# PROC054D_AWR_2_AWR_3_LP87524P.net
KiCad netlist of a schematic drawn in Altium Designer
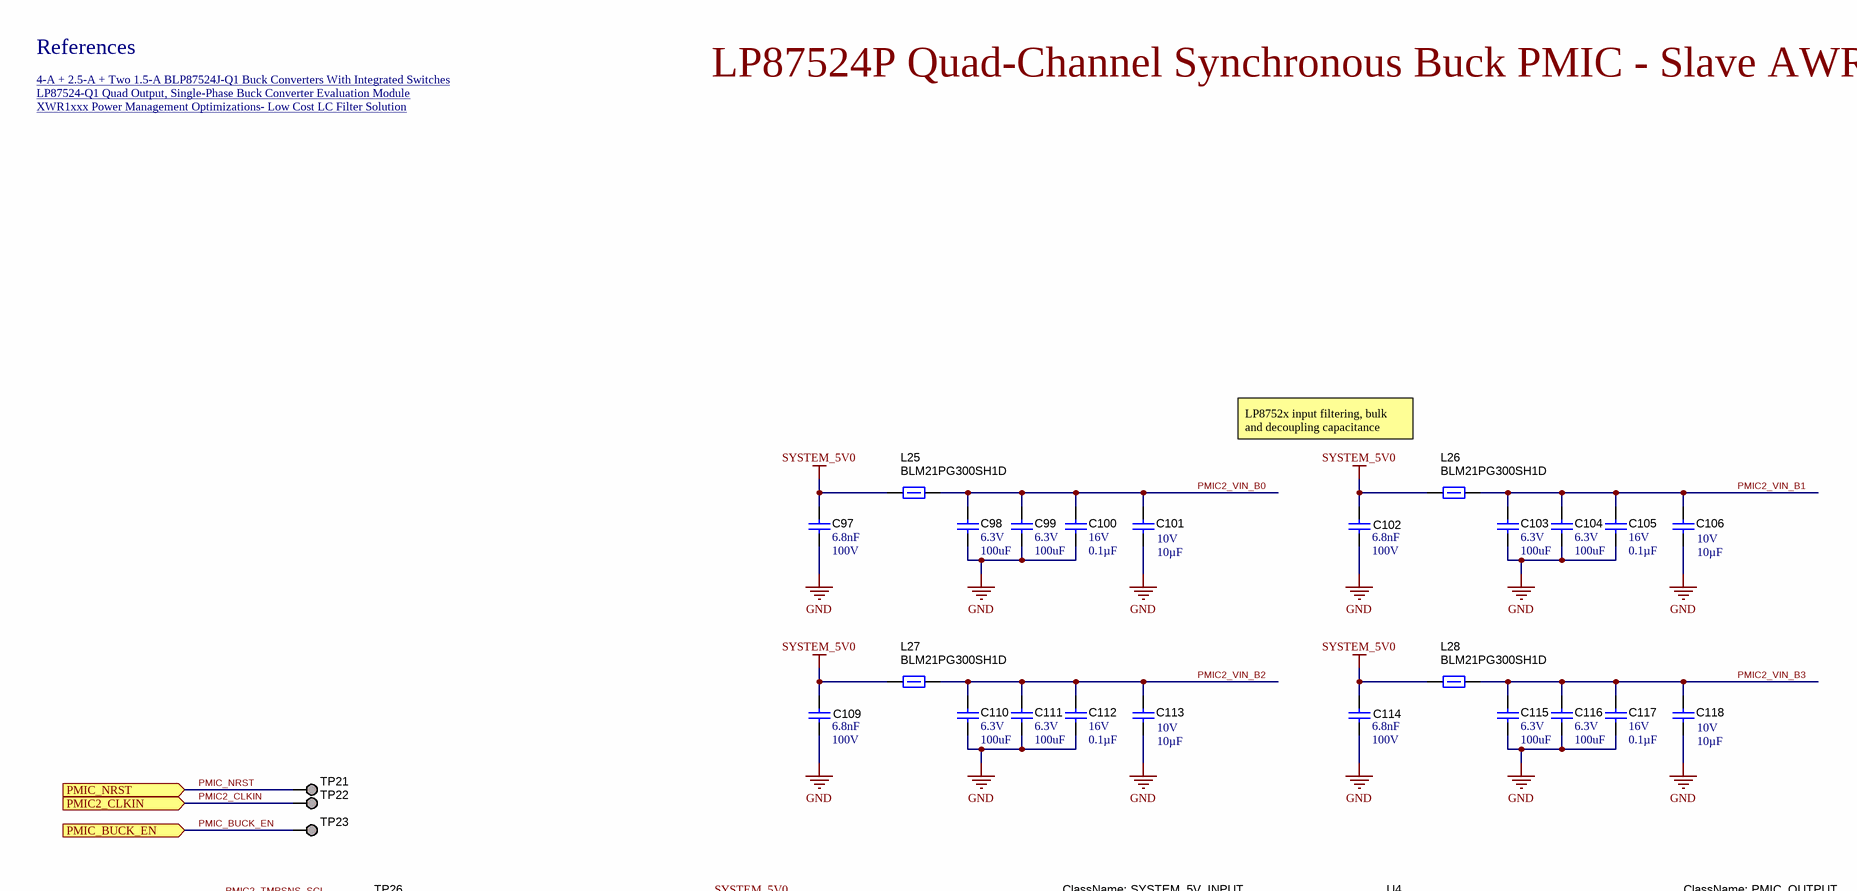
[diagram p0: PROC054D_AWR_2_AWR_3_LP87524P.SchDoc, top left]
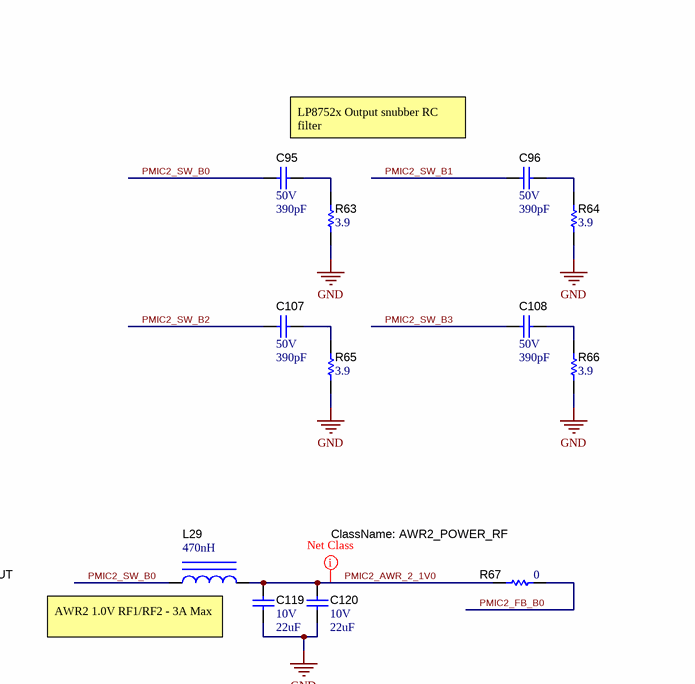
[diagram p1: PROC054D_AWR_2_AWR_3_LP87524P.SchDoc, top right]
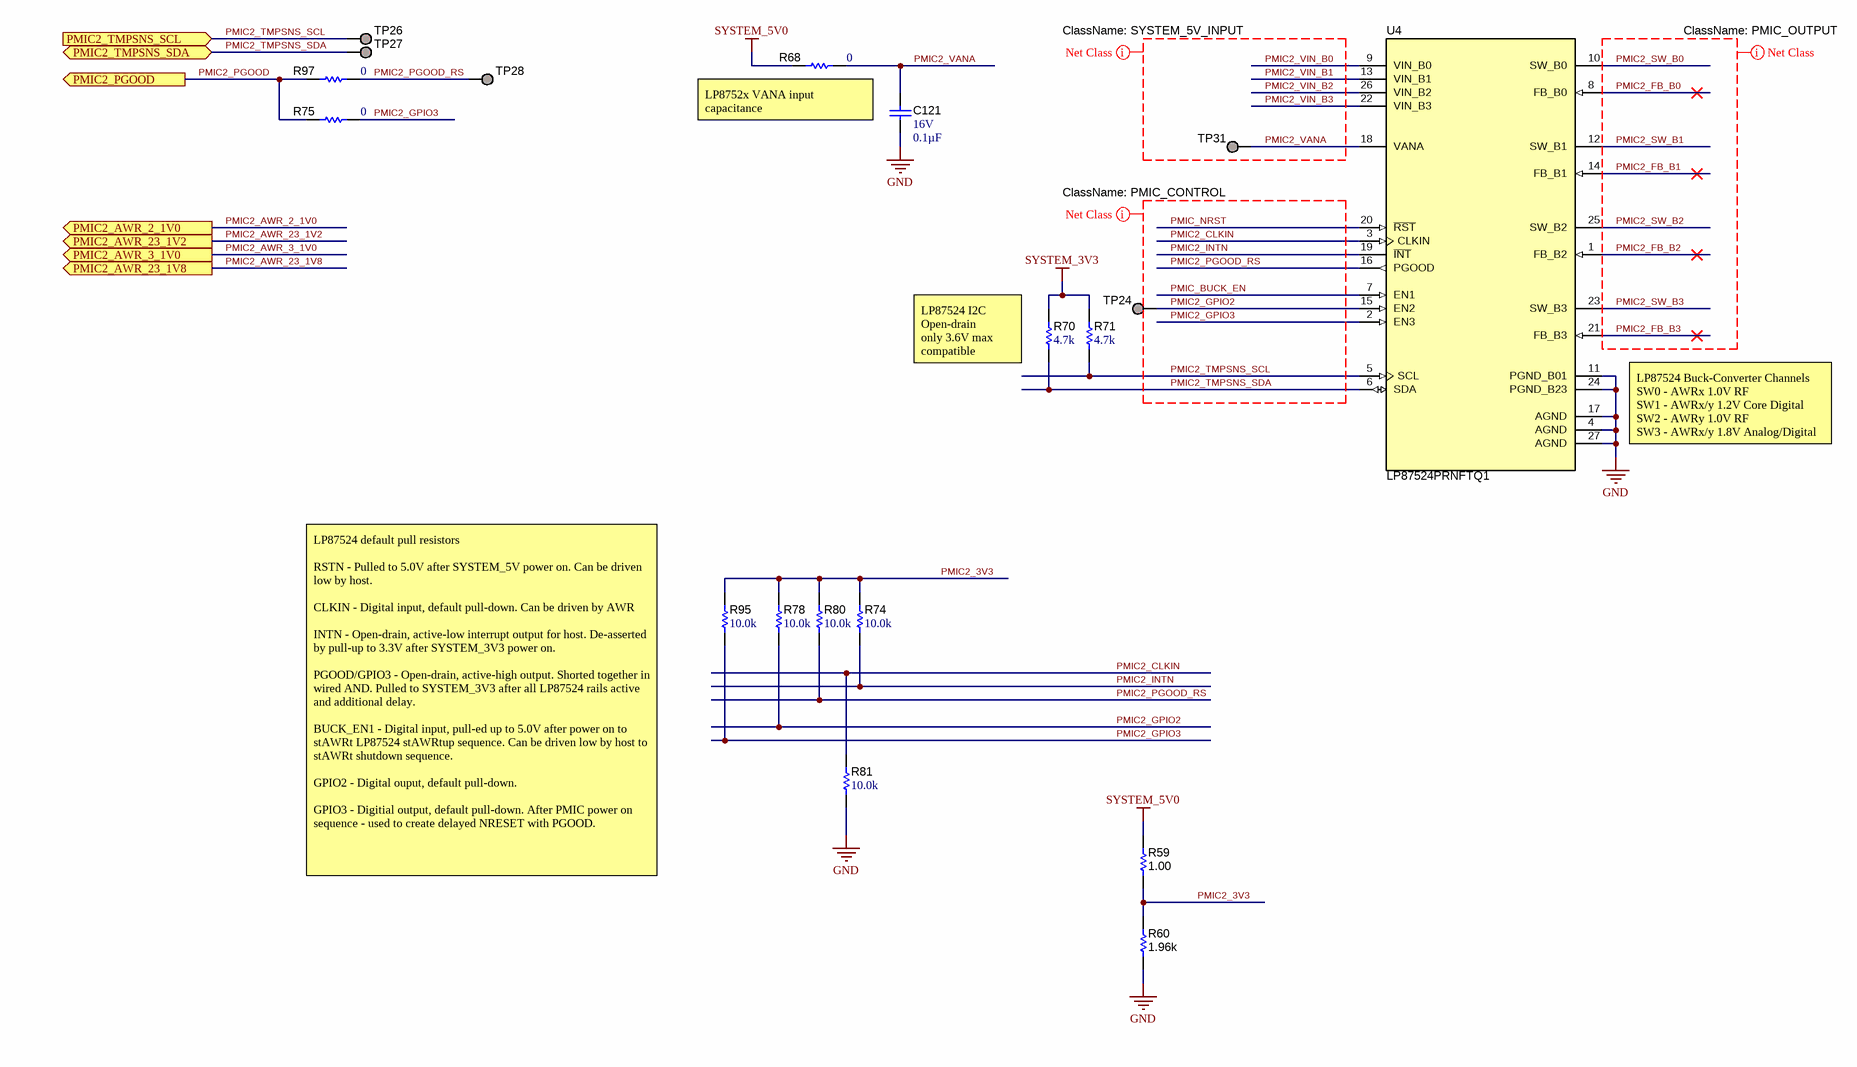
[diagram p2: PROC054D_AWR_2_AWR_3_LP87524P.SchDoc, bottom left]
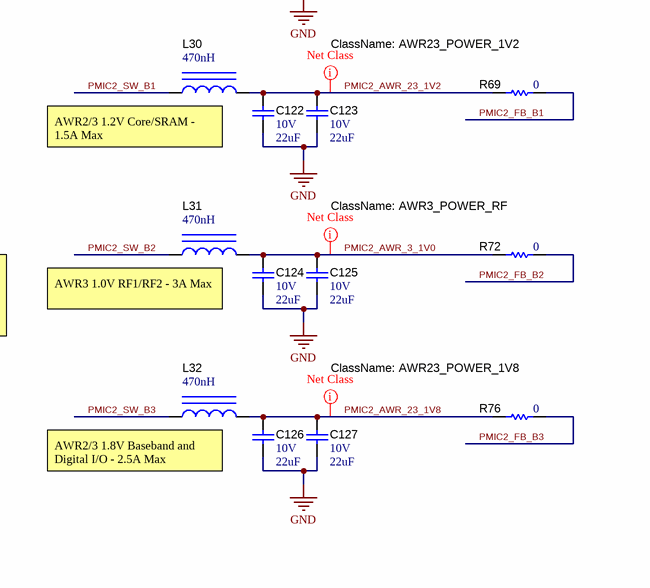
[diagram p3: PROC054D_AWR_2_AWR_3_LP87524P.SchDoc, bottom right]

(export (version "E")
  (design (tool "Eeschema 10.0.6"))
  (components
    (comp (ref "C95")
      (value "GCM155R71H391KA37D")
      (footprint "0402S")
      (description "CAP, CERM, 390 pF, 50 V,+/- 10%, X7R, AEC-Q200 Grade 1, 0402")
      (fields
        (field (name "MANUFACTURER") "MuRata")
        (field (name "VDC_V") "50V")
        (field (name "VALUEDISPLAYED") "390pF")
      )
      (libsource (lib "Altium Vault - TI") (part "Capacitor"))
    )
    (comp (ref "C96")
      (value "GCM155R71H391KA37D")
      (footprint "0402S")
      (description "CAP, CERM, 390 pF, 50 V,+/- 10%, X7R, AEC-Q200 Grade 1, 0402")
      (fields
        (field (name "MANUFACTURER") "MuRata")
        (field (name "VDC_V") "50V")
        (field (name "VALUEDISPLAYED") "390pF")
      )
      (libsource (lib "Altium Vault - TI") (part "Capacitor"))
    )
    (comp (ref "C97")
      (value "GCM188R72A682KA37D")
      (footprint "0603S")
      (description "CAP, CERM, 6800 pF, 100 V,+/- 10%, X7R, AEC-Q200 Grade 1, 0603")
      (fields
        (field (name "CAP_F") "6.8nF")
        (field (name "VDC_V") "100V")
        (field (name "MANUFACTURER") "MuRata")
      )
      (libsource (lib "Altium Vault - TI") (part "Capacitor"))
    )
    (comp (ref "C98")
      (value "GRM21BR60J107M")
      (footprint "0805L")
      (description "CAP, CERM, 100 uF, 6.3 V, +/- 20%, X5R, 0805")
      (fields
        (field (name "MANUFACTURER") "MuRata")
        (field (name "VDC_V") "6.3V")
        (field (name "VALUEDISPLAYED") "100uF")
        (field (name "PUBLISHER") "Texas Instruments")
      )
      (libsource (lib "Altium Vault - TI") (part "Capacitor"))
    )
    (comp (ref "C99")
      (value "GRM21BR60J107M")
      (footprint "0805L")
      (description "CAP, CERM, 100 uF, 6.3 V, +/- 20%, X5R, 0805")
      (fields
        (field (name "MANUFACTURER") "MuRata")
        (field (name "VDC_V") "6.3V")
        (field (name "VALUEDISPLAYED") "100uF")
        (field (name "PUBLISHER") "Texas Instruments")
      )
      (libsource (lib "Altium Vault - TI") (part "Capacitor"))
    )
    (comp (ref "C100")
      (value "GCM155R71C104JA55D")
      (footprint "0402S")
      (description "CAP, CERM, 0.1 µF, 16 V,+/- 5%, X7R, AEC-Q200 Grade 1, 0402")
      (fields
        (field (name "MANUFACTURER") "MuRata")
        (field (name "VDC_V") "16V")
        (field (name "VALUEDISPLAYED") "0.1µF")
      )
      (libsource (lib "Altium Vault - TI") (part "Capacitor"))
    )
    (comp (ref "C101")
      (value "GRM21BR71A106KA73L")
      (footprint "0805L")
      (description "CAP, CERM, 10 µF,  V,+/- 10%, X7R, 0805")
      (fields
        (field (name "MANUFACTURER") "MuRata")
        (field (name "CAP_F") "10µF")
        (field (name "VDC_V") "10V")
      )
      (libsource (lib "Altium Vault - TI") (part "Capacitor"))
    )
    (comp (ref "C102")
      (value "GCM188R72A682KA37D")
      (footprint "0603S")
      (description "CAP, CERM, 6800 pF, 100 V,+/- 10%, X7R, AEC-Q200 Grade 1, 0603")
      (fields
        (field (name "CAP_F") "6.8nF")
        (field (name "VDC_V") "100V")
        (field (name "MANUFACTURER") "MuRata")
      )
      (libsource (lib "Altium Vault - TI") (part "Capacitor"))
    )
    (comp (ref "C103")
      (value "GRM21BR60J107M")
      (footprint "0805L")
      (description "CAP, CERM, 100 uF, 6.3 V, +/- 20%, X5R, 0805")
      (fields
        (field (name "MANUFACTURER") "MuRata")
        (field (name "VDC_V") "6.3V")
        (field (name "VALUEDISPLAYED") "100uF")
        (field (name "PUBLISHER") "Texas Instruments")
      )
      (libsource (lib "Altium Vault - TI") (part "Capacitor"))
    )
    (comp (ref "C104")
      (value "GRM21BR60J107M")
      (footprint "0805L")
      (description "CAP, CERM, 100 uF, 6.3 V, +/- 20%, X5R, 0805")
      (fields
        (field (name "MANUFACTURER") "MuRata")
        (field (name "VDC_V") "6.3V")
        (field (name "VALUEDISPLAYED") "100uF")
        (field (name "PUBLISHER") "Texas Instruments")
      )
      (libsource (lib "Altium Vault - TI") (part "Capacitor"))
    )
    (comp (ref "C105")
      (value "GCM155R71C104JA55D")
      (footprint "0402S")
      (description "CAP, CERM, 0.1 µF, 16 V,+/- 5%, X7R, AEC-Q200 Grade 1, 0402")
      (fields
        (field (name "MANUFACTURER") "MuRata")
        (field (name "VDC_V") "16V")
        (field (name "VALUEDISPLAYED") "0.1µF")
      )
      (libsource (lib "Altium Vault - TI") (part "Capacitor"))
    )
    (comp (ref "C106")
      (value "GRM21BR71A106KA73L")
      (footprint "0805L")
      (description "CAP, CERM, 10 µF,  V,+/- 10%, X7R, 0805")
      (fields
        (field (name "MANUFACTURER") "MuRata")
        (field (name "CAP_F") "10µF")
        (field (name "VDC_V") "10V")
      )
      (libsource (lib "Altium Vault - TI") (part "Capacitor"))
    )
    (comp (ref "C107")
      (value "GCM155R71H391KA37D")
      (footprint "0402S")
      (description "CAP, CERM, 390 pF, 50 V,+/- 10%, X7R, AEC-Q200 Grade 1, 0402")
      (fields
        (field (name "MANUFACTURER") "MuRata")
        (field (name "VDC_V") "50V")
        (field (name "VALUEDISPLAYED") "390pF")
      )
      (libsource (lib "Altium Vault - TI") (part "Capacitor"))
    )
    (comp (ref "C108")
      (value "GCM155R71H391KA37D")
      (footprint "0402S")
      (description "CAP, CERM, 390 pF, 50 V,+/- 10%, X7R, AEC-Q200 Grade 1, 0402")
      (fields
        (field (name "MANUFACTURER") "MuRata")
        (field (name "VDC_V") "50V")
        (field (name "VALUEDISPLAYED") "390pF")
      )
      (libsource (lib "Altium Vault - TI") (part "Capacitor"))
    )
    (comp (ref "C109")
      (value "GCM188R72A682KA37D")
      (footprint "0603S")
      (description "CAP, CERM, 6800 pF, 100 V,+/- 10%, X7R, AEC-Q200 Grade 1, 0603")
      (fields
        (field (name "CAP_F") "6.8nF")
        (field (name "VDC_V") "100V")
        (field (name "MANUFACTURER") "MuRata")
      )
      (libsource (lib "Altium Vault - TI") (part "Capacitor"))
    )
    (comp (ref "C110")
      (value "GRM21BR60J107M")
      (footprint "0805L")
      (description "CAP, CERM, 100 uF, 6.3 V, +/- 20%, X5R, 0805")
      (fields
        (field (name "MANUFACTURER") "MuRata")
        (field (name "VDC_V") "6.3V")
        (field (name "VALUEDISPLAYED") "100uF")
        (field (name "PUBLISHER") "Texas Instruments")
      )
      (libsource (lib "Altium Vault - TI") (part "Capacitor"))
    )
    (comp (ref "C111")
      (value "GRM21BR60J107M")
      (footprint "0805L")
      (description "CAP, CERM, 100 uF, 6.3 V, +/- 20%, X5R, 0805")
      (fields
        (field (name "MANUFACTURER") "MuRata")
        (field (name "VDC_V") "6.3V")
        (field (name "VALUEDISPLAYED") "100uF")
        (field (name "PUBLISHER") "Texas Instruments")
      )
      (libsource (lib "Altium Vault - TI") (part "Capacitor"))
    )
    (comp (ref "C112")
      (value "GCM155R71C104JA55D")
      (footprint "0402S")
      (description "CAP, CERM, 0.1 µF, 16 V,+/- 5%, X7R, AEC-Q200 Grade 1, 0402")
      (fields
        (field (name "MANUFACTURER") "MuRata")
        (field (name "VDC_V") "16V")
        (field (name "VALUEDISPLAYED") "0.1µF")
      )
      (libsource (lib "Altium Vault - TI") (part "Capacitor"))
    )
    (comp (ref "C113")
      (value "GRM21BR71A106KA73L")
      (footprint "0805L")
      (description "CAP, CERM, 10 µF,  V,+/- 10%, X7R, 0805")
      (fields
        (field (name "MANUFACTURER") "MuRata")
        (field (name "CAP_F") "10µF")
        (field (name "VDC_V") "10V")
      )
      (libsource (lib "Altium Vault - TI") (part "Capacitor"))
    )
    (comp (ref "C114")
      (value "GCM188R72A682KA37D")
      (footprint "0603S")
      (description "CAP, CERM, 6800 pF, 100 V,+/- 10%, X7R, AEC-Q200 Grade 1, 0603")
      (fields
        (field (name "CAP_F") "6.8nF")
        (field (name "VDC_V") "100V")
        (field (name "MANUFACTURER") "MuRata")
      )
      (libsource (lib "Altium Vault - TI") (part "Capacitor"))
    )
    (comp (ref "C115")
      (value "GRM21BR60J107M")
      (footprint "0805L")
      (description "CAP, CERM, 100 uF, 6.3 V, +/- 20%, X5R, 0805")
      (fields
        (field (name "MANUFACTURER") "MuRata")
        (field (name "VDC_V") "6.3V")
        (field (name "VALUEDISPLAYED") "100uF")
        (field (name "PUBLISHER") "Texas Instruments")
      )
      (libsource (lib "Altium Vault - TI") (part "Capacitor"))
    )
    (comp (ref "C116")
      (value "GRM21BR60J107M")
      (footprint "0805L")
      (description "CAP, CERM, 100 uF, 6.3 V, +/- 20%, X5R, 0805")
      (fields
        (field (name "MANUFACTURER") "MuRata")
        (field (name "VDC_V") "6.3V")
        (field (name "VALUEDISPLAYED") "100uF")
        (field (name "PUBLISHER") "Texas Instruments")
      )
      (libsource (lib "Altium Vault - TI") (part "Capacitor"))
    )
    (comp (ref "C117")
      (value "GCM155R71C104JA55D")
      (footprint "0402S")
      (description "CAP, CERM, 0.1 µF, 16 V,+/- 5%, X7R, AEC-Q200 Grade 1, 0402")
      (fields
        (field (name "MANUFACTURER") "MuRata")
        (field (name "VDC_V") "16V")
        (field (name "VALUEDISPLAYED") "0.1µF")
      )
      (libsource (lib "Altium Vault - TI") (part "Capacitor"))
    )
    (comp (ref "C118")
      (value "GRM21BR71A106KA73L")
      (footprint "0805L")
      (description "CAP, CERM, 10 µF,  V,+/- 10%, X7R, 0805")
      (fields
        (field (name "MANUFACTURER") "MuRata")
        (field (name "CAP_F") "10µF")
        (field (name "VDC_V") "10V")
      )
      (libsource (lib "Altium Vault - TI") (part "Capacitor"))
    )
    (comp (ref "C119")
      (value "C2012X7S1A226M125AC")
      (footprint "0805L")
      (description "CAP, CERM, 22 uF, 10 V, +/- 20%, X7S, 0805")
      (fields
        (field (name "MANUFACTURER") "TDK")
        (field (name "VDC_V") "10V")
        (field (name "VALUEDISPLAYED") "22uF")
        (field (name "PUBLISHER") "Texas Instruments")
      )
      (libsource (lib "Altium Vault - TI") (part "Capacitor"))
    )
    (comp (ref "C120")
      (value "C2012X7S1A226M125AC")
      (footprint "0805L")
      (description "CAP, CERM, 22 uF, 10 V, +/- 20%, X7S, 0805")
      (fields
        (field (name "MANUFACTURER") "TDK")
        (field (name "VDC_V") "10V")
        (field (name "VALUEDISPLAYED") "22uF")
        (field (name "PUBLISHER") "Texas Instruments")
      )
      (libsource (lib "Altium Vault - TI") (part "Capacitor"))
    )
    (comp (ref "C121")
      (value "GCM155R71C104JA55D")
      (footprint "0402S")
      (description "CAP, CERM, 0.1 µF, 16 V,+/- 5%, X7R, AEC-Q200 Grade 1, 0402")
      (fields
        (field (name "MANUFACTURER") "MuRata")
        (field (name "VDC_V") "16V")
        (field (name "VALUEDISPLAYED") "0.1µF")
      )
      (libsource (lib "Altium Vault - TI") (part "Capacitor"))
    )
    (comp (ref "C122")
      (value "C2012X7S1A226M125AC")
      (footprint "0805L")
      (description "CAP, CERM, 22 uF, 10 V, +/- 20%, X7S, 0805")
      (fields
        (field (name "MANUFACTURER") "TDK")
        (field (name "VDC_V") "10V")
        (field (name "VALUEDISPLAYED") "22uF")
        (field (name "PUBLISHER") "Texas Instruments")
      )
      (libsource (lib "Altium Vault - TI") (part "Capacitor"))
    )
    (comp (ref "C123")
      (value "C2012X7S1A226M125AC")
      (footprint "0805L")
      (description "CAP, CERM, 22 uF, 10 V, +/- 20%, X7S, 0805")
      (fields
        (field (name "MANUFACTURER") "TDK")
        (field (name "VDC_V") "10V")
        (field (name "VALUEDISPLAYED") "22uF")
        (field (name "PUBLISHER") "Texas Instruments")
      )
      (libsource (lib "Altium Vault - TI") (part "Capacitor"))
    )
    (comp (ref "C124")
      (value "C2012X7S1A226M125AC")
      (footprint "0805L")
      (description "CAP, CERM, 22 uF, 10 V, +/- 20%, X7S, 0805")
      (fields
        (field (name "MANUFACTURER") "TDK")
        (field (name "VDC_V") "10V")
        (field (name "VALUEDISPLAYED") "22uF")
        (field (name "PUBLISHER") "Texas Instruments")
      )
      (libsource (lib "Altium Vault - TI") (part "Capacitor"))
    )
    (comp (ref "C125")
      (value "C2012X7S1A226M125AC")
      (footprint "0805L")
      (description "CAP, CERM, 22 uF, 10 V, +/- 20%, X7S, 0805")
      (fields
        (field (name "MANUFACTURER") "TDK")
        (field (name "VDC_V") "10V")
        (field (name "VALUEDISPLAYED") "22uF")
        (field (name "PUBLISHER") "Texas Instruments")
      )
      (libsource (lib "Altium Vault - TI") (part "Capacitor"))
    )
    (comp (ref "C126")
      (value "C2012X7S1A226M125AC")
      (footprint "0805L")
      (description "CAP, CERM, 22 uF, 10 V, +/- 20%, X7S, 0805")
      (fields
        (field (name "MANUFACTURER") "TDK")
        (field (name "VDC_V") "10V")
        (field (name "VALUEDISPLAYED") "22uF")
        (field (name "PUBLISHER") "Texas Instruments")
      )
      (libsource (lib "Altium Vault - TI") (part "Capacitor"))
    )
    (comp (ref "C127")
      (value "C2012X7S1A226M125AC")
      (footprint "0805L")
      (description "CAP, CERM, 22 uF, 10 V, +/- 20%, X7S, 0805")
      (fields
        (field (name "MANUFACTURER") "TDK")
        (field (name "VDC_V") "10V")
        (field (name "VALUEDISPLAYED") "22uF")
        (field (name "PUBLISHER") "Texas Instruments")
      )
      (libsource (lib "Altium Vault - TI") (part "Capacitor"))
    )
    (comp (ref "L25")
      (value "BLM21PG300SH1D")
      (footprint "0805_HV")
      (description "Ferrite Bead, 30 ohm @ 100 MHz, 4 A, 0805")
      (fields (field (name "MANUFACTURER") "MuRata") (field (name "PUBLISHER") "Texas Instruments"))
      (libsource (lib "Altium Vault - TI") (part "Ferrite_Bead"))
    )
    (comp (ref "L26")
      (value "BLM21PG300SH1D")
      (footprint "0805_HV")
      (description "Ferrite Bead, 30 ohm @ 100 MHz, 4 A, 0805")
      (fields (field (name "MANUFACTURER") "MuRata") (field (name "PUBLISHER") "Texas Instruments"))
      (libsource (lib "Altium Vault - TI") (part "Ferrite_Bead"))
    )
    (comp (ref "L27")
      (value "BLM21PG300SH1D")
      (footprint "0805_HV")
      (description "Ferrite Bead, 30 ohm @ 100 MHz, 4 A, 0805")
      (fields (field (name "MANUFACTURER") "MuRata") (field (name "PUBLISHER") "Texas Instruments"))
      (libsource (lib "Altium Vault - TI") (part "Ferrite_Bead"))
    )
    (comp (ref "L28")
      (value "BLM21PG300SH1D")
      (footprint "0805_HV")
      (description "Ferrite Bead, 30 ohm @ 100 MHz, 4 A, 0805")
      (fields (field (name "MANUFACTURER") "MuRata") (field (name "PUBLISHER") "Texas Instruments"))
      (libsource (lib "Altium Vault - TI") (part "Ferrite_Bead"))
    )
    (comp (ref "L29")
      (value "DFE252012PD-R47M")
      (footprint "DFE252012P")
      (description "Inductor, Shielded, 470 nH, 4.7 A, 0.021 ohm, SMD")
      (fields
        (field (name "MANUFACTURER") "MuRata Toko")
        (field (name "VALUEDISPLAYED") "470nH")
        (field (name "PUBLISHER") "Texas Instruments")
      )
      (libsource (lib "Altium Vault - TI") (part "Inductor_Iron"))
    )
    (comp (ref "L30")
      (value "DFE252012PD-R47M")
      (footprint "DFE252012P")
      (description "Inductor, Shielded, 470 nH, 4.7 A, 0.021 ohm, SMD")
      (fields
        (field (name "MANUFACTURER") "MuRata Toko")
        (field (name "VALUEDISPLAYED") "470nH")
        (field (name "PUBLISHER") "Texas Instruments")
      )
      (libsource (lib "Altium Vault - TI") (part "Inductor_Iron"))
    )
    (comp (ref "L31")
      (value "DFE252012PD-R47M")
      (footprint "DFE252012P")
      (description "Inductor, Shielded, 470 nH, 4.7 A, 0.021 ohm, SMD")
      (fields
        (field (name "MANUFACTURER") "MuRata Toko")
        (field (name "VALUEDISPLAYED") "470nH")
        (field (name "PUBLISHER") "Texas Instruments")
      )
      (libsource (lib "Altium Vault - TI") (part "Inductor_Iron"))
    )
    (comp (ref "L32")
      (value "DFE252012PD-R47M")
      (footprint "DFE252012P")
      (description "Inductor, Shielded, 470 nH, 4.7 A, 0.021 ohm, SMD")
      (fields
        (field (name "MANUFACTURER") "MuRata Toko")
        (field (name "VALUEDISPLAYED") "470nH")
        (field (name "PUBLISHER") "Texas Instruments")
      )
      (libsource (lib "Altium Vault - TI") (part "Inductor_Iron"))
    )
    (comp (ref "R59")
      (value "CRCW06031R00FKEA")
      (footprint "0603")
      (description "RES, 1.00, 1%, 0.1 W, AEC-Q200 Grade 0, 0603")
      (fields (field (name "MANUFACTURER") "Vishay-Dale") (field (name "VALUEDISPLAYED") "1.00"))
      (libsource (lib "Altium Vault - TI") (part "Resistor"))
    )
    (comp (ref "R60")
      (value "CRCW06031K96FKEA")
      (footprint "0603")
      (description "RES, 1.96 k, 1%, 0.1 W, AEC-Q200 Grade 0, 0603")
      (fields (field (name "MANUFACTURER") "Vishay-Dale") (field (name "VALUEDISPLAYED") "1.96k"))
      (libsource (lib "Altium Vault - TI") (part "Resistor"))
    )
    (comp (ref "R63")
      (value "CRCW04023R90JNED")
      (footprint "0402S")
      (description "RES, 3.9, 5%, 0.063 W, AEC-Q200 Grade 0, 0402")
      (fields (field (name "MANUFACTURER") "Vishay-Dale") (field (name "VALUEDISPLAYED") "3.9"))
      (libsource (lib "Altium Vault - TI") (part "Resistor"))
    )
    (comp (ref "R64")
      (value "CRCW04023R90JNED")
      (footprint "0402S")
      (description "RES, 3.9, 5%, 0.063 W, AEC-Q200 Grade 0, 0402")
      (fields (field (name "MANUFACTURER") "Vishay-Dale") (field (name "VALUEDISPLAYED") "3.9"))
      (libsource (lib "Altium Vault - TI") (part "Resistor"))
    )
    (comp (ref "R65")
      (value "CRCW04023R90JNED")
      (footprint "0402S")
      (description "RES, 3.9, 5%, 0.063 W, AEC-Q200 Grade 0, 0402")
      (fields (field (name "MANUFACTURER") "Vishay-Dale") (field (name "VALUEDISPLAYED") "3.9"))
      (libsource (lib "Altium Vault - TI") (part "Resistor"))
    )
    (comp (ref "R66")
      (value "CRCW04023R90JNED")
      (footprint "0402S")
      (description "RES, 3.9, 5%, 0.063 W, AEC-Q200 Grade 0, 0402")
      (fields (field (name "MANUFACTURER") "Vishay-Dale") (field (name "VALUEDISPLAYED") "3.9"))
      (libsource (lib "Altium Vault - TI") (part "Resistor"))
    )
    (comp (ref "R67")
      (value "CRCW04020000Z0ED")
      (footprint "0402S")
      (description "RES, 0, 5%, 0.063 W, AEC-Q200 Grade 0, 0402")
      (fields (field (name "MANUFACTURER") "Vishay-Dale") (field (name "VALUEDISPLAYED") "0"))
      (libsource (lib "Altium Vault - TI") (part "Resistor"))
    )
    (comp (ref "R68")
      (value "MCT06030Z0000ZP500")
      (footprint "0603S")
      (description "RES, 0, 5%, 0.125 W, 0603")
      (fields
        (field (name "MANUFACTURER") "Vishay/Beyschlag")
        (field (name "VALUEDISPLAYED") "0")
        (field (name "PUBLISHER") "Texas Instruments")
      )
      (libsource (lib "Altium Vault - TI") (part "Resistor"))
    )
    (comp (ref "R69")
      (value "CRCW04020000Z0ED")
      (footprint "0402S")
      (description "RES, 0, 5%, 0.063 W, AEC-Q200 Grade 0, 0402")
      (fields (field (name "MANUFACTURER") "Vishay-Dale") (field (name "VALUEDISPLAYED") "0"))
      (libsource (lib "Altium Vault - TI") (part "Resistor"))
    )
    (comp (ref "R70")
      (value "CRCW04024K70JNED")
      (footprint "0402")
      (description "RES, 4.7 k, 5%, 0.063 W, AEC-Q200 Grade 0, 0402")
      (fields (field (name "MANUFACTURER") "Vishay-Dale") (field (name "VALUEDISPLAYED") "4.7k"))
      (libsource (lib "Altium Vault - TI") (part "Resistor"))
    )
    (comp (ref "R71")
      (value "CRCW04024K70JNED")
      (footprint "0402")
      (description "RES, 4.7 k, 5%, 0.063 W, AEC-Q200 Grade 0, 0402")
      (fields (field (name "MANUFACTURER") "Vishay-Dale") (field (name "VALUEDISPLAYED") "4.7k"))
      (libsource (lib "Altium Vault - TI") (part "Resistor"))
    )
    (comp (ref "R72")
      (value "CRCW04020000Z0ED")
      (footprint "0402S")
      (description "RES, 0, 5%, 0.063 W, AEC-Q200 Grade 0, 0402")
      (fields (field (name "MANUFACTURER") "Vishay-Dale") (field (name "VALUEDISPLAYED") "0"))
      (libsource (lib "Altium Vault - TI") (part "Resistor"))
    )
    (comp (ref "R74")
      (value "CRCW040210K0FKED")
      (footprint "0402")
      (description "RES, 10.0 k, 1%, 0.063 W, AEC-Q200 Grade 0, 0402")
      (fields (field (name "MANUFACTURER") "Vishay-Dale") (field (name "VALUEDISPLAYED") "10.0k"))
      (libsource (lib "Altium Vault - TI") (part "Resistor"))
    )
    (comp (ref "R75")
      (value "MCT06030Z0000ZP500")
      (footprint "0603")
      (description "RES, 0, 5%, 0.125 W, 0603")
      (fields
        (field (name "MANUFACTURER") "Vishay/Beyschlag")
        (field (name "VALUEDISPLAYED") "0")
        (field (name "PUBLISHER") "Texas Instruments")
      )
      (libsource (lib "Altium Vault - TI") (part "Resistor"))
    )
    (comp (ref "R76")
      (value "CRCW04020000Z0ED")
      (footprint "0402S")
      (description "RES, 0, 5%, 0.063 W, AEC-Q200 Grade 0, 0402")
      (fields (field (name "MANUFACTURER") "Vishay-Dale") (field (name "VALUEDISPLAYED") "0"))
      (libsource (lib "Altium Vault - TI") (part "Resistor"))
    )
    (comp (ref "R78")
      (value "CRCW040210K0FKED")
      (footprint "0402S")
      (description "RES, 10.0 k, 1%, 0.063 W, AEC-Q200 Grade 0, 0402")
      (fields (field (name "MANUFACTURER") "Vishay-Dale") (field (name "VALUEDISPLAYED") "10.0k"))
      (libsource (lib "Altium Vault - TI") (part "Resistor"))
    )
    (comp (ref "R80")
      (value "CRCW040210K0FKED")
      (footprint "0402")
      (description "RES, 10.0 k, 1%, 0.063 W, AEC-Q200 Grade 0, 0402")
      (fields (field (name "MANUFACTURER") "Vishay-Dale") (field (name "VALUEDISPLAYED") "10.0k"))
      (libsource (lib "Altium Vault - TI") (part "Resistor"))
    )
    (comp (ref "R81")
      (value "CRCW040210K0FKED")
      (footprint "0402")
      (description "RES, 10.0 k, 1%, 0.063 W, AEC-Q200 Grade 0, 0402")
      (fields (field (name "MANUFACTURER") "Vishay-Dale") (field (name "VALUEDISPLAYED") "10.0k"))
      (libsource (lib "Altium Vault - TI") (part "Resistor"))
    )
    (comp (ref "R95")
      (value "CRCW040210K0FKED")
      (footprint "0402")
      (description "RES, 10.0 k, 1%, 0.063 W, AEC-Q200 Grade 0, 0402")
      (fields (field (name "MANUFACTURER") "Vishay-Dale") (field (name "VALUEDISPLAYED") "10.0k"))
      (libsource (lib "Altium Vault - TI") (part "Resistor"))
    )
    (comp (ref "R97")
      (value "MCT06030Z0000ZP500")
      (footprint "0603")
      (description "RES, 0, 5%, 0.125 W, 0603")
      (fields
        (field (name "MANUFACTURER") "Vishay/Beyschlag")
        (field (name "VALUEDISPLAYED") "0")
        (field (name "PUBLISHER") "Texas Instruments")
      )
      (libsource (lib "Altium Vault - TI") (part "Resistor"))
    )
    (comp (ref "TP21")
      (value "TP_SM_1MM")
      (footprint "TP_SM_1MM")
      (description "1mm Test Point, SMT")
      (fields (field (name "MANUFACTURER") "Any") (field (name "PUBLISHER") "Texas Instruments"))
      (libsource (lib "Altium Vault - TI") (part "CMP-0003825-1"))
    )
    (comp (ref "TP22")
      (value "TP_SM_1MM")
      (footprint "TP_SM_1MM")
      (description "1mm Test Point, SMT")
      (fields (field (name "MANUFACTURER") "Any") (field (name "PUBLISHER") "Texas Instruments"))
      (libsource (lib "Altium Vault - TI") (part "CMP-0003825-1"))
    )
    (comp (ref "TP23")
      (value "TP_SM_1MM")
      (footprint "TP_SM_1MM")
      (description "1mm Test Point, SMT")
      (fields (field (name "MANUFACTURER") "Any") (field (name "PUBLISHER") "Texas Instruments"))
      (libsource (lib "Altium Vault - TI") (part "CMP-0003825-1"))
    )
    (comp (ref "TP24")
      (value "TP_SM_1MM")
      (footprint "TP_SM_1MM")
      (description "1mm Test Point, SMT")
      (fields (field (name "MANUFACTURER") "Any") (field (name "PUBLISHER") "Texas Instruments"))
      (libsource (lib "Altium Vault - TI") (part "CMP-0003825-1"))
    )
    (comp (ref "TP26")
      (value "TP_SM_1MM")
      (footprint "TP_SM_1MM")
      (description "1mm Test Point, SMT")
      (fields (field (name "MANUFACTURER") "Any") (field (name "PUBLISHER") "Texas Instruments"))
      (libsource (lib "Altium Vault - TI") (part "CMP-0003825-1"))
    )
    (comp (ref "TP27")
      (value "TP_SM_1MM")
      (footprint "TP_SM_1MM")
      (description "1mm Test Point, SMT")
      (fields (field (name "MANUFACTURER") "Any") (field (name "PUBLISHER") "Texas Instruments"))
      (libsource (lib "Altium Vault - TI") (part "CMP-0003825-1"))
    )
    (comp (ref "TP28")
      (value "TP_SM_1MM")
      (footprint "TP_SM_1MM")
      (description "1mm Test Point, SMT")
      (fields (field (name "MANUFACTURER") "Any") (field (name "PUBLISHER") "Texas Instruments"))
      (libsource (lib "Altium Vault - TI") (part "CMP-0003825-1"))
    )
    (comp (ref "TP31")
      (value "TP_SM_1MM")
      (footprint "TP_SM_1MM")
      (description "1mm Test Point, SMT")
      (fields (field (name "MANUFACTURER") "Any") (field (name "PUBLISHER") "Texas Instruments"))
      (libsource (lib "Altium Vault - TI") (part "CMP-0003825-1"))
    )
    (comp (ref "U4")
      (value "LP87524PRNFTQ1")
      (footprint "RNF0026C")
      (description "4-A + 2.5-A + Two 1.5-A Buck Converters With Integrated Switches, RNF0026C (VQFN-HR-26)")
      (fields
        (field (name "ALTERNATE PARTNUMBER") "LP87524PRNFRQ1")
        (field (name "MANUFACTURER") "Texas Instruments")
        (field (name "PARTNUMBER") "LP87524PRNFTQ1")
      )
      (libsource (lib "Altium Vault - TI") (part "CMP-0083823-1"))
    )
  )
  (nets
    (net (code "1") (name "/PMIC2_3V3") (class "Default")
      (node (ref "R59") (pin "1") (pinfunction "1_1") (pintype "passive"))
      (node (ref "R60") (pin "2") (pinfunction "2_2") (pintype "passive"))
      (node (ref "R74") (pin "2") (pinfunction "2_2") (pintype "passive"))
      (node (ref "R78") (pin "2") (pinfunction "2_2") (pintype "passive"))
      (node (ref "R80") (pin "2") (pinfunction "2_2") (pintype "passive"))
      (node (ref "R95") (pin "2") (pinfunction "2_2") (pintype "passive"))
    )
    (net (code "2") (name "/PMIC2_AWR_2_1V0") (class "Default")
      (node (ref "C119") (pin "1") (pinfunction "1_1") (pintype "passive"))
      (node (ref "C120") (pin "1") (pinfunction "1_1") (pintype "passive"))
      (node (ref "L29") (pin "2") (pinfunction "2_2") (pintype "passive"))
      (node (ref "R67") (pin "1") (pinfunction "1_1") (pintype "passive"))
    )
    (net (code "3") (name "/PMIC2_AWR_3_1V0") (class "Default")
      (node (ref "C124") (pin "1") (pinfunction "1_1") (pintype "passive"))
      (node (ref "C125") (pin "1") (pinfunction "1_1") (pintype "passive"))
      (node (ref "L31") (pin "2") (pinfunction "2_2") (pintype "passive"))
      (node (ref "R72") (pin "1") (pinfunction "1_1") (pintype "passive"))
    )
    (net (code "4") (name "/PMIC2_AWR_23_1V2") (class "Default")
      (node (ref "C122") (pin "1") (pinfunction "1_1") (pintype "passive"))
      (node (ref "C123") (pin "1") (pinfunction "1_1") (pintype "passive"))
      (node (ref "L30") (pin "2") (pinfunction "2_2") (pintype "passive"))
      (node (ref "R69") (pin "1") (pinfunction "1_1") (pintype "passive"))
    )
    (net (code "5") (name "/PMIC2_AWR_23_1V8") (class "Default")
      (node (ref "C126") (pin "1") (pinfunction "1_1") (pintype "passive"))
      (node (ref "C127") (pin "1") (pinfunction "1_1") (pintype "passive"))
      (node (ref "L32") (pin "2") (pinfunction "2_2") (pintype "passive"))
      (node (ref "R76") (pin "1") (pinfunction "1_1") (pintype "passive"))
    )
    (net (code "6") (name "/PMIC2_CLKIN") (class "Default")
      (node (ref "R81") (pin "2") (pinfunction "2_2") (pintype "passive"))
      (node (ref "TP22") (pin "1") (pintype "passive"))
      (node (ref "U4") (pin "3") (pinfunction "CLKIN_3") (pintype "input"))
    )
    (net (code "7") (name "/PMIC2_FB_B0") (class "Default")
      (node (ref "R67") (pin "2") (pinfunction "2_2") (pintype "passive"))
      (node (ref "U4") (pin "8") (pinfunction "FB_B0_8") (pintype "input"))
    )
    (net (code "8") (name "/PMIC2_FB_B1") (class "Default")
      (node (ref "R69") (pin "2") (pinfunction "2_2") (pintype "passive"))
      (node (ref "U4") (pin "14") (pinfunction "FB_B1_14") (pintype "input"))
    )
    (net (code "9") (name "/PMIC2_FB_B2") (class "Default")
      (node (ref "R72") (pin "2") (pinfunction "2_2") (pintype "passive"))
      (node (ref "U4") (pin "1") (pinfunction "FB_B2_1") (pintype "input"))
    )
    (net (code "10") (name "/PMIC2_FB_B3") (class "Default")
      (node (ref "R76") (pin "2") (pinfunction "2_2") (pintype "passive"))
      (node (ref "U4") (pin "21") (pinfunction "FB_B3_21") (pintype "input"))
    )
    (net (code "11") (name "/PMIC2_GPIO2") (class "Default")
      (node (ref "R78") (pin "1") (pinfunction "1_1") (pintype "passive"))
      (node (ref "TP24") (pin "1") (pintype "passive"))
      (node (ref "U4") (pin "15") (pinfunction "EN2_15") (pintype "input"))
    )
    (net (code "12") (name "/PMIC2_GPIO3") (class "Default")
      (node (ref "R75") (pin "2") (pinfunction "2_2") (pintype "passive"))
      (node (ref "R95") (pin "1") (pinfunction "1_1") (pintype "passive"))
      (node (ref "U4") (pin "2") (pinfunction "EN3_2") (pintype "input"))
    )
    (net (code "13") (name "/PMIC2_INTN") (class "Default")
      (node (ref "R74") (pin "1") (pinfunction "1_1") (pintype "passive"))
      (node (ref "U4") (pin "19") (pinfunction "INT_19") (pintype "open_collector"))
    )
    (net (code "14") (name "/PMIC2_PGOOD") (class "Default")
      (node (ref "R75") (pin "1") (pinfunction "1_1") (pintype "passive"))
      (node (ref "R97") (pin "1") (pinfunction "1_1") (pintype "passive"))
    )
    (net (code "15") (name "/PMIC2_PGOOD_RS") (class "Default")
      (node (ref "R80") (pin "1") (pinfunction "1_1") (pintype "passive"))
      (node (ref "R97") (pin "2") (pinfunction "2_2") (pintype "passive"))
      (node (ref "TP28") (pin "1") (pintype "passive"))
      (node (ref "U4") (pin "16") (pinfunction "PGOOD_16") (pintype "output"))
    )
    (net (code "16") (name "/PMIC2_SW_B0") (class "Default")
      (node (ref "C95") (pin "1") (pinfunction "1_1") (pintype "passive"))
      (node (ref "L29") (pin "1") (pinfunction "1_1") (pintype "passive"))
      (node (ref "U4") (pin "10") (pinfunction "SW_B0_10") (pintype "power_in"))
    )
    (net (code "17") (name "/PMIC2_SW_B1") (class "Default")
      (node (ref "C96") (pin "1") (pinfunction "1_1") (pintype "passive"))
      (node (ref "L30") (pin "1") (pinfunction "1_1") (pintype "passive"))
      (node (ref "U4") (pin "12") (pinfunction "SW_B1_12") (pintype "power_in"))
    )
    (net (code "18") (name "/PMIC2_SW_B2") (class "Default")
      (node (ref "C107") (pin "1") (pinfunction "1_1") (pintype "passive"))
      (node (ref "L31") (pin "1") (pinfunction "1_1") (pintype "passive"))
      (node (ref "U4") (pin "25") (pinfunction "SW_B2_25") (pintype "power_in"))
    )
    (net (code "19") (name "/PMIC2_SW_B3") (class "Default")
      (node (ref "C108") (pin "1") (pinfunction "1_1") (pintype "passive"))
      (node (ref "L32") (pin "1") (pinfunction "1_1") (pintype "passive"))
      (node (ref "U4") (pin "23") (pinfunction "SW_B3_23") (pintype "power_in"))
    )
    (net (code "20") (name "/PMIC2_TMPSNS_SCL") (class "Default")
      (node (ref "R71") (pin "1") (pinfunction "1_1") (pintype "passive"))
      (node (ref "TP26") (pin "1") (pintype "passive"))
      (node (ref "U4") (pin "5") (pinfunction "SCL_5") (pintype "input"))
    )
    (net (code "21") (name "/PMIC2_TMPSNS_SDA") (class "Default")
      (node (ref "R70") (pin "2") (pinfunction "2_2") (pintype "passive"))
      (node (ref "TP27") (pin "1") (pintype "passive"))
      (node (ref "U4") (pin "6") (pinfunction "SDA_6") (pintype "bidirectional"))
    )
    (net (code "22") (name "/PMIC2_VANA") (class "Default")
      (node (ref "C121") (pin "1") (pinfunction "1_1") (pintype "passive"))
      (node (ref "R68") (pin "2") (pinfunction "2_2") (pintype "passive"))
      (node (ref "TP31") (pin "1") (pintype "passive"))
      (node (ref "U4") (pin "18") (pinfunction "VANA_18") (pintype "power_in"))
    )
    (net (code "23") (name "/PMIC2_VIN_B0") (class "Default")
      (node (ref "C100") (pin "1") (pinfunction "1_1") (pintype "passive"))
      (node (ref "C101") (pin "1") (pinfunction "1_1") (pintype "passive"))
      (node (ref "C98") (pin "1") (pinfunction "1_1") (pintype "passive"))
      (node (ref "C99") (pin "1") (pinfunction "1_1") (pintype "passive"))
      (node (ref "L25") (pin "2") (pinfunction "2_2") (pintype "passive"))
      (node (ref "U4") (pin "9") (pinfunction "VIN_B0_9") (pintype "power_in"))
    )
    (net (code "24") (name "/PMIC2_VIN_B1") (class "Default")
      (node (ref "C103") (pin "1") (pinfunction "1_1") (pintype "passive"))
      (node (ref "C104") (pin "1") (pinfunction "1_1") (pintype "passive"))
      (node (ref "C105") (pin "1") (pinfunction "1_1") (pintype "passive"))
      (node (ref "C106") (pin "1") (pinfunction "1_1") (pintype "passive"))
      (node (ref "L26") (pin "2") (pinfunction "2_2") (pintype "passive"))
      (node (ref "U4") (pin "13") (pinfunction "VIN_B1_13") (pintype "power_in"))
    )
    (net (code "25") (name "/PMIC2_VIN_B2") (class "Default")
      (node (ref "C110") (pin "1") (pinfunction "1_1") (pintype "passive"))
      (node (ref "C111") (pin "1") (pinfunction "1_1") (pintype "passive"))
      (node (ref "C112") (pin "1") (pinfunction "1_1") (pintype "passive"))
      (node (ref "C113") (pin "1") (pinfunction "1_1") (pintype "passive"))
      (node (ref "L27") (pin "2") (pinfunction "2_2") (pintype "passive"))
      (node (ref "U4") (pin "26") (pinfunction "VIN_B2_26") (pintype "power_in"))
    )
    (net (code "26") (name "/PMIC2_VIN_B3") (class "Default")
      (node (ref "C115") (pin "1") (pinfunction "1_1") (pintype "passive"))
      (node (ref "C116") (pin "1") (pinfunction "1_1") (pintype "passive"))
      (node (ref "C117") (pin "1") (pinfunction "1_1") (pintype "passive"))
      (node (ref "C118") (pin "1") (pinfunction "1_1") (pintype "passive"))
      (node (ref "L28") (pin "2") (pinfunction "2_2") (pintype "passive"))
      (node (ref "U4") (pin "22") (pinfunction "VIN_B3_22") (pintype "power_in"))
    )
    (net (code "27") (name "/PMIC_BUCK_EN") (class "Default")
      (node (ref "TP23") (pin "1") (pintype "passive"))
      (node (ref "U4") (pin "7") (pinfunction "EN1_7") (pintype "input"))
    )
    (net (code "28") (name "/PMIC_NRST") (class "Default")
      (node (ref "TP21") (pin "1") (pintype "passive"))
      (node (ref "U4") (pin "20") (pinfunction "RST_20") (pintype "input"))
    )
    (net (code "29") (name "GND") (class "Default")
      (node (ref "C100") (pin "2") (pinfunction "2_2") (pintype "passive"))
      (node (ref "C101") (pin "2") (pinfunction "2_2") (pintype "passive"))
      (node (ref "C102") (pin "2") (pinfunction "2_2") (pintype "passive"))
      (node (ref "C103") (pin "2") (pinfunction "2_2") (pintype "passive"))
      (node (ref "C104") (pin "2") (pinfunction "2_2") (pintype "passive"))
      (node (ref "C105") (pin "2") (pinfunction "2_2") (pintype "passive"))
      (node (ref "C106") (pin "2") (pinfunction "2_2") (pintype "passive"))
      (node (ref "C109") (pin "2") (pinfunction "2_2") (pintype "passive"))
      (node (ref "C110") (pin "2") (pinfunction "2_2") (pintype "passive"))
      (node (ref "C111") (pin "2") (pinfunction "2_2") (pintype "passive"))
      (node (ref "C112") (pin "2") (pinfunction "2_2") (pintype "passive"))
      (node (ref "C113") (pin "2") (pinfunction "2_2") (pintype "passive"))
      (node (ref "C114") (pin "2") (pinfunction "2_2") (pintype "passive"))
      (node (ref "C115") (pin "2") (pinfunction "2_2") (pintype "passive"))
      (node (ref "C116") (pin "2") (pinfunction "2_2") (pintype "passive"))
      (node (ref "C117") (pin "2") (pinfunction "2_2") (pintype "passive"))
      (node (ref "C118") (pin "2") (pinfunction "2_2") (pintype "passive"))
      (node (ref "C119") (pin "2") (pinfunction "2_2") (pintype "passive"))
      (node (ref "C120") (pin "2") (pinfunction "2_2") (pintype "passive"))
      (node (ref "C121") (pin "2") (pinfunction "2_2") (pintype "passive"))
      (node (ref "C122") (pin "2") (pinfunction "2_2") (pintype "passive"))
      (node (ref "C123") (pin "2") (pinfunction "2_2") (pintype "passive"))
      (node (ref "C124") (pin "2") (pinfunction "2_2") (pintype "passive"))
      (node (ref "C125") (pin "2") (pinfunction "2_2") (pintype "passive"))
      (node (ref "C126") (pin "2") (pinfunction "2_2") (pintype "passive"))
      (node (ref "C127") (pin "2") (pinfunction "2_2") (pintype "passive"))
      (node (ref "C97") (pin "2") (pinfunction "2_2") (pintype "passive"))
      (node (ref "C98") (pin "2") (pinfunction "2_2") (pintype "passive"))
      (node (ref "C99") (pin "2") (pinfunction "2_2") (pintype "passive"))
      (node (ref "R60") (pin "1") (pinfunction "1_1") (pintype "passive"))
      (node (ref "R63") (pin "1") (pinfunction "1_1") (pintype "passive"))
      (node (ref "R64") (pin "1") (pinfunction "1_1") (pintype "passive"))
      (node (ref "R65") (pin "1") (pinfunction "1_1") (pintype "passive"))
      (node (ref "R66") (pin "1") (pinfunction "1_1") (pintype "passive"))
      (node (ref "R81") (pin "1") (pinfunction "1_1") (pintype "passive"))
      (node (ref "U4") (pin "11") (pinfunction "PGND_B01_11") (pintype "power_in"))
      (node (ref "U4") (pin "17") (pinfunction "AGND_17") (pintype "power_in"))
      (node (ref "U4") (pin "24") (pinfunction "PGND_B23_24") (pintype "power_in"))
      (node (ref "U4") (pin "27") (pinfunction "AGND_27") (pintype "power_in"))
      (node (ref "U4") (pin "4") (pinfunction "AGND_4") (pintype "power_in"))
    )
    (net (code "30") (name "Net-(C95-Pad2)") (class "Default")
      (node (ref "C95") (pin "2") (pinfunction "2_2") (pintype "passive"))
      (node (ref "R63") (pin "2") (pinfunction "2_2") (pintype "passive"))
    )
    (net (code "31") (name "Net-(C96-Pad2)") (class "Default")
      (node (ref "C96") (pin "2") (pinfunction "2_2") (pintype "passive"))
      (node (ref "R64") (pin "2") (pinfunction "2_2") (pintype "passive"))
    )
    (net (code "32") (name "Net-(C107-Pad2)") (class "Default")
      (node (ref "C107") (pin "2") (pinfunction "2_2") (pintype "passive"))
      (node (ref "R65") (pin "2") (pinfunction "2_2") (pintype "passive"))
    )
    (net (code "33") (name "Net-(C108-Pad2)") (class "Default")
      (node (ref "C108") (pin "2") (pinfunction "2_2") (pintype "passive"))
      (node (ref "R66") (pin "2") (pinfunction "2_2") (pintype "passive"))
    )
    (net (code "34") (name "SYSTEM_3V3") (class "Default")
      (node (ref "R70") (pin "1") (pinfunction "1_1") (pintype "passive"))
      (node (ref "R71") (pin "2") (pinfunction "2_2") (pintype "passive"))
    )
    (net (code "35") (name "SYSTEM_5V0") (class "Default")
      (node (ref "C102") (pin "1") (pinfunction "1_1") (pintype "passive"))
      (node (ref "C109") (pin "1") (pinfunction "1_1") (pintype "passive"))
      (node (ref "C114") (pin "1") (pinfunction "1_1") (pintype "passive"))
      (node (ref "C97") (pin "1") (pinfunction "1_1") (pintype "passive"))
      (node (ref "L25") (pin "1") (pinfunction "1_1") (pintype "passive"))
      (node (ref "L26") (pin "1") (pinfunction "1_1") (pintype "passive"))
      (node (ref "L27") (pin "1") (pinfunction "1_1") (pintype "passive"))
      (node (ref "L28") (pin "1") (pinfunction "1_1") (pintype "passive"))
      (node (ref "R59") (pin "2") (pinfunction "2_2") (pintype "passive"))
      (node (ref "R68") (pin "1") (pinfunction "1_1") (pintype "passive"))
    )
  )
)
